# Drive.net
KiCad netlist of a schematic drawn in Altium Designer
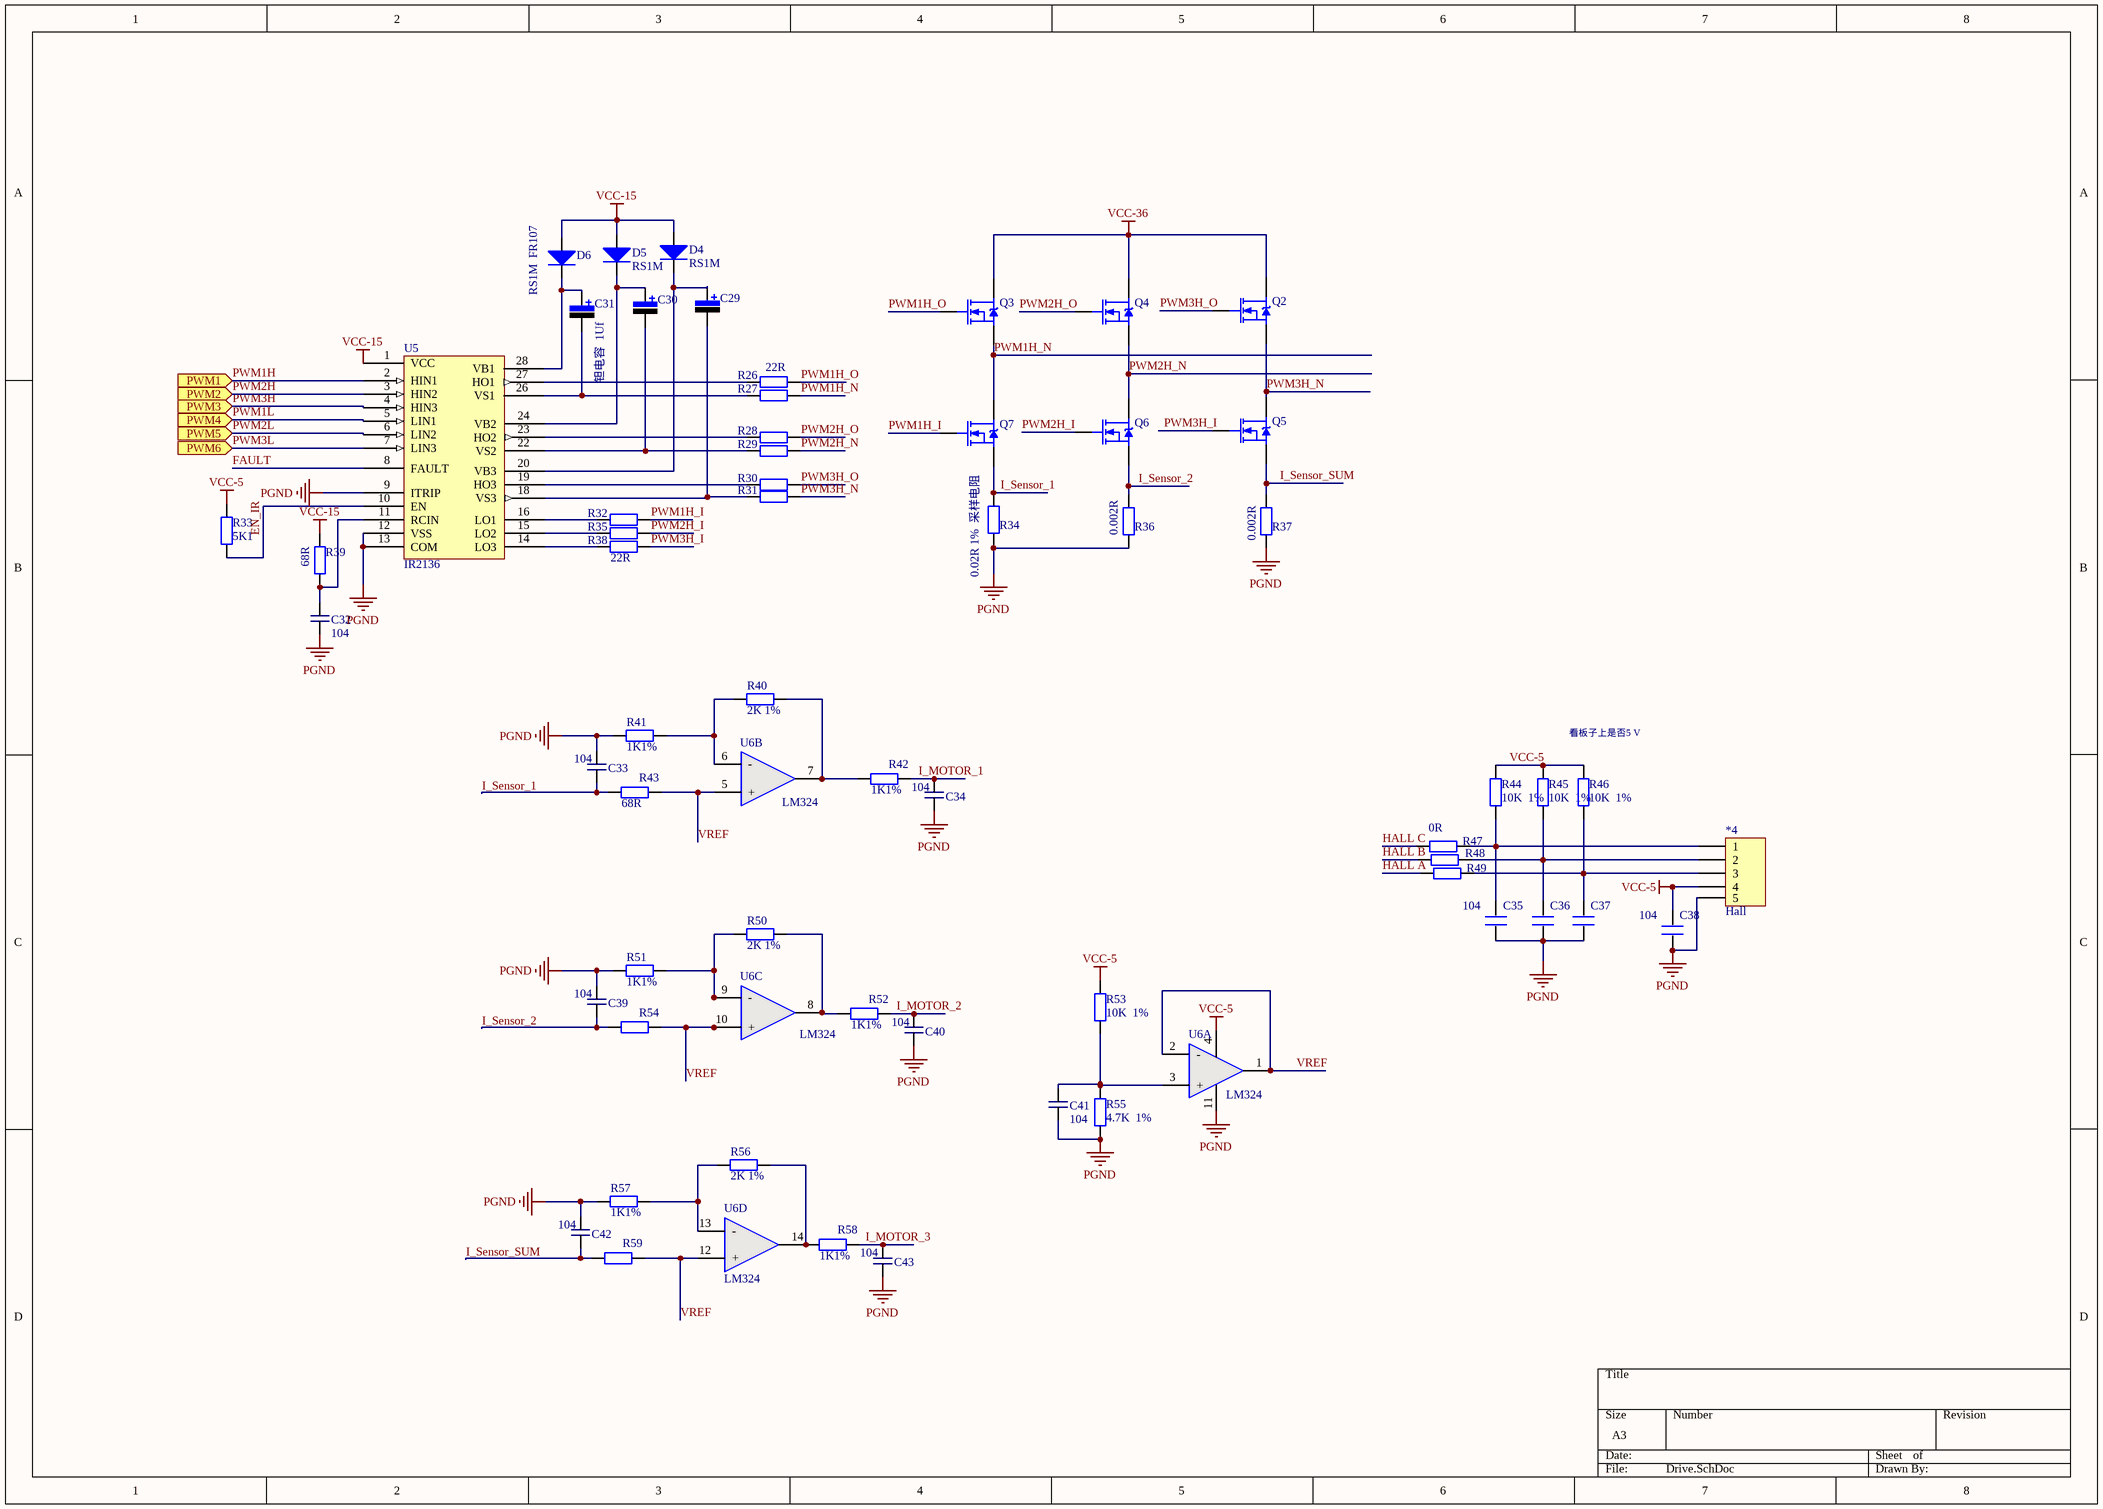
[diagram p0: Drive.SchDoc]

(export (version "E")
  (design (tool "Eeschema 10.0.6"))
  (components
    (comp (ref "*4") (value "Hall") (footprint "普通五口接线柱") (libsource (lib "MySchlib") (part "Head_5")))
    (comp (ref "C29") (value "钽电容") (footprint "3216A  Ta") (libsource (lib "MySchlib") (part "Cap_2")))
    (comp (ref "C30") (value "钽电容") (footprint "3216A  Ta") (libsource (lib "MySchlib") (part "Cap_2")))
    (comp (ref "C31")
      (value "钽电容  1Uf")
      (footprint "3216A  Ta")
      (description "钽电容")
      (libsource (lib "MySchlib") (part "Cap_2"))
    )
    (comp (ref "C32") (value "104") (footprint "0603- C") (libsource (lib "MySchlib") (part "Cap")))
    (comp (ref "C33") (value "104") (footprint "0603- C") (libsource (lib "MySchlib") (part "Cap")))
    (comp (ref "C34") (value "104") (footprint "0603- C") (libsource (lib "MySchlib") (part "Cap")))
    (comp (ref "C35") (value "104") (footprint "0603- C") (libsource (lib "MiniSTM32底板_SCH") (part "C")))
    (comp (ref "C36") (value "104") (footprint "0603- C") (libsource (lib "MiniSTM32底板_SCH") (part "C")))
    (comp (ref "C37") (value "104") (footprint "0603- C") (libsource (lib "MiniSTM32底板_SCH") (part "C")))
    (comp (ref "C38") (value "104") (footprint "0603- C") (libsource (lib "MiniSTM32底板_SCH") (part "C")))
    (comp (ref "C39") (value "104") (footprint "0603- C") (libsource (lib "MySchlib") (part "Cap")))
    (comp (ref "C40") (value "104") (footprint "0603- C") (libsource (lib "MySchlib") (part "Cap")))
    (comp (ref "C41") (value "104") (footprint "0603- C") (libsource (lib "MySchlib") (part "Cap")))
    (comp (ref "C42") (value "104") (footprint "0603- C") (libsource (lib "MySchlib") (part "Cap")))
    (comp (ref "C43") (value "104") (footprint "0603- C") (libsource (lib "MySchlib") (part "Cap")))
    (comp (ref "D4")
      (value "RS1M")
      (footprint "D RS1M")
      (description "二极管")
      (libsource (lib "MySchlib") (part "D_1"))
    )
    (comp (ref "D5")
      (value "RS1M")
      (footprint "D RS1M")
      (description "二极管")
      (libsource (lib "MySchlib") (part "D_1"))
    )
    (comp (ref "D6")
      (value "RS1M  FR107")
      (footprint "D RS1M")
      (description "二极管")
      (libsource (lib "MySchlib") (part "D_1"))
    )
    (comp (ref "Q2")
      (value "IRF540NS")
      (footprint "TO-220AB  MOS")
      (description "MOS")
      (libsource (lib "MySchlib") (part "IRF540NS"))
    )
    (comp (ref "Q3")
      (value "IRF540NS")
      (footprint "TO-220AB  MOS")
      (description "MOS")
      (libsource (lib "MySchlib") (part "IRF540NS"))
    )
    (comp (ref "Q4")
      (value "IRF540NS")
      (footprint "TO-220AB  MOS")
      (description "MOS")
      (libsource (lib "MySchlib") (part "IRF540NS"))
    )
    (comp (ref "Q5")
      (value "IRF540NS")
      (footprint "TO-220AB  MOS")
      (description "MOS")
      (libsource (lib "MySchlib") (part "IRF540NS"))
    )
    (comp (ref "Q6")
      (value "IRF540NS")
      (footprint "TO-220AB  MOS")
      (description "MOS")
      (libsource (lib "MySchlib") (part "IRF540NS"))
    )
    (comp (ref "Q7")
      (value "IRF540NS")
      (footprint "TO-220AB  MOS")
      (description "MOS")
      (libsource (lib "MySchlib") (part "IRF540NS"))
    )
    (comp (ref "R26") (value "22R") (footprint "0805R") (libsource (lib "MySchlib") (part "R")))
    (comp (ref "R27") (value "68R") (footprint "0805R") (libsource (lib "MySchlib") (part "R")))
    (comp (ref "R28") (value "68R") (footprint "0805R") (libsource (lib "MySchlib") (part "R")))
    (comp (ref "R29") (value "68R") (footprint "0805R") (libsource (lib "MySchlib") (part "R")))
    (comp (ref "R30") (value "68R") (footprint "0805R") (libsource (lib "MySchlib") (part "R")))
    (comp (ref "R31") (value "68R") (footprint "0805R") (libsource (lib "MySchlib") (part "R")))
    (comp (ref "R32") (value "68R") (footprint "0805R") (libsource (lib "MySchlib") (part "R")))
    (comp (ref "R33") (value "5K1") (footprint "0603-R") (libsource (lib "") (part "R_2")))
    (comp (ref "R34") (value "0.02R 1%  采样电阻") (footprint "2512R") (libsource (lib "") (part "R_3")))
    (comp (ref "R35") (value "68R") (footprint "0805R") (libsource (lib "MySchlib") (part "R")))
    (comp (ref "R36") (value "0.002R") (footprint "2512R") (libsource (lib "") (part "R_3")))
    (comp (ref "R37") (value "0.002R") (footprint "2512R") (libsource (lib "") (part "R_3")))
    (comp (ref "R38") (value "22R") (footprint "0805R") (libsource (lib "MySchlib") (part "R")))
    (comp (ref "R39") (value "68R") (footprint "0603-R") (libsource (lib "") (part "R_2")))
    (comp (ref "R40") (value "2K 1%") (footprint "0603-R") (libsource (lib "") (part "R_1")))
    (comp (ref "R41") (value "1K1%") (footprint "0603-R") (libsource (lib "") (part "R_1")))
    (comp (ref "R42") (value "1K1%") (footprint "0603-R") (libsource (lib "") (part "R_1")))
    (comp (ref "R43") (value "68R") (footprint "0603-R") (libsource (lib "") (part "R_1")))
    (comp (ref "R44") (value "10K  1%") (footprint "0603-R") (libsource (lib "") (part "R_2")))
    (comp (ref "R45") (value "10K  1%") (footprint "0603-R") (libsource (lib "") (part "R_2")))
    (comp (ref "R46") (value "10K  1%") (footprint "0603-R") (libsource (lib "") (part "R_2")))
    (comp (ref "R47") (value "0R") (footprint "0603-R") (libsource (lib "MySchlib") (part "R")))
    (comp (ref "R48") (value "R") (footprint "0603-R") (libsource (lib "MySchlib") (part "R")))
    (comp (ref "R49") (value "R") (footprint "0603-R") (libsource (lib "MySchlib") (part "R")))
    (comp (ref "R50") (value "2K 1%") (footprint "0603-R") (libsource (lib "") (part "R_1")))
    (comp (ref "R51") (value "1K1%") (footprint "0603-R") (libsource (lib "") (part "R_1")))
    (comp (ref "R52") (value "1K1%") (footprint "0603-R") (libsource (lib "") (part "R_1")))
    (comp (ref "R53") (value "10K  1%") (footprint "0603-R") (libsource (lib "") (part "R_2")))
    (comp (ref "R54") (value "1K1%") (footprint "0603-R") (libsource (lib "") (part "R_1")))
    (comp (ref "R55") (value "4.7K  1%") (footprint "0603-R") (libsource (lib "") (part "R_2")))
    (comp (ref "R56") (value "2K 1%") (footprint "0603-R") (libsource (lib "") (part "R_1")))
    (comp (ref "R57") (value "1K1%") (footprint "0603-R") (libsource (lib "") (part "R_1")))
    (comp (ref "R58") (value "1K1%") (footprint "0603-R") (libsource (lib "") (part "R_1")))
    (comp (ref "R59") (value "1K1%") (footprint "0603-R") (libsource (lib "") (part "R_1")))
    (comp (ref "U5")
      (value "IR2136")
      (footprint "IR2136S SOIC-28")
      (libsource (lib "MySchlib") (part "IR2136"))
    )
    (comp (ref "U6")
      (value "LM324")
      (footprint "SOP-14N")
      (description "4运放SOP8芯片")
      (libsource (lib "MySchlib") (part "LM324"))
    )
  )
  (nets
    (net (code "1") (name "/EN_IR") (class "Default")
      (node (ref "R33") (pin "2") (pinfunction "2_2") (pintype "passive"))
      (node (ref "U5") (pin "10") (pinfunction "EN_10") (pintype "passive"))
    )
    (net (code "2") (name "/FAULT") (class "Default")
      (node (ref "U5") (pin "8") (pinfunction "FAULT_8") (pintype "passive"))
    )
    (net (code "3") (name "/HALL A") (class "Default")
      (node (ref "R49") (pin "1") (pinfunction "1_1") (pintype "passive"))
    )
    (net (code "4") (name "/HALL B") (class "Default")
      (node (ref "R48") (pin "1") (pinfunction "1_1") (pintype "passive"))
    )
    (net (code "5") (name "/HALL C") (class "Default")
      (node (ref "R47") (pin "1") (pinfunction "1_1") (pintype "passive"))
    )
    (net (code "6") (name "/I_MOTOR_1") (class "Default")
      (node (ref "C34") (pin "1") (pinfunction "1_1") (pintype "passive"))
      (node (ref "R42") (pin "1") (pinfunction "1_1") (pintype "passive"))
    )
    (net (code "7") (name "/I_MOTOR_2") (class "Default")
      (node (ref "C40") (pin "1") (pinfunction "1_1") (pintype "passive"))
      (node (ref "R52") (pin "1") (pinfunction "1_1") (pintype "passive"))
    )
    (net (code "8") (name "/I_MOTOR_3") (class "Default")
      (node (ref "C43") (pin "1") (pinfunction "1_1") (pintype "passive"))
      (node (ref "R58") (pin "1") (pinfunction "1_1") (pintype "passive"))
    )
    (net (code "9") (name "/I_Sensor_1") (class "Default")
      (node (ref "C33") (pin "2") (pinfunction "2_2") (pintype "passive"))
      (node (ref "Q7") (pin "S") (pinfunction "S_S") (pintype "passive"))
      (node (ref "R34") (pin "2") (pinfunction "2_2") (pintype "passive"))
      (node (ref "R43") (pin "2") (pinfunction "2_2") (pintype "passive"))
    )
    (net (code "10") (name "/I_Sensor_2") (class "Default")
      (node (ref "C39") (pin "2") (pinfunction "2_2") (pintype "passive"))
      (node (ref "Q6") (pin "S") (pinfunction "S_S") (pintype "passive"))
      (node (ref "R36") (pin "2") (pinfunction "2_2") (pintype "passive"))
      (node (ref "R54") (pin "2") (pinfunction "2_2") (pintype "passive"))
    )
    (net (code "11") (name "/I_Sensor_SUM") (class "Default")
      (node (ref "C42") (pin "2") (pinfunction "2_2") (pintype "passive"))
      (node (ref "Q5") (pin "S") (pinfunction "S_S") (pintype "passive"))
      (node (ref "R37") (pin "2") (pinfunction "2_2") (pintype "passive"))
      (node (ref "R59") (pin "2") (pinfunction "2_2") (pintype "passive"))
    )
    (net (code "12") (name "/PWM1H") (class "Default")
      (node (ref "U5") (pin "2") (pinfunction "HIN1_2") (pintype "input"))
    )
    (net (code "13") (name "/PWM1H_I") (class "Default")
      (node (ref "Q7") (pin "G") (pinfunction "G_G") (pintype "passive"))
      (node (ref "R32") (pin "2") (pinfunction "2_2") (pintype "passive"))
    )
    (net (code "14") (name "/PWM1H_N") (class "Default")
      (node (ref "Q3") (pin "S") (pinfunction "S_S") (pintype "passive"))
      (node (ref "Q7") (pin "D") (pinfunction "D_D") (pintype "passive"))
      (node (ref "R27") (pin "2") (pinfunction "2_2") (pintype "passive"))
    )
    (net (code "15") (name "/PWM1H_O") (class "Default")
      (node (ref "Q3") (pin "G") (pinfunction "G_G") (pintype "passive"))
      (node (ref "R26") (pin "2") (pinfunction "2_2") (pintype "passive"))
    )
    (net (code "16") (name "/PWM1L") (class "Default")
      (node (ref "U5") (pin "5") (pinfunction "LIN1_5") (pintype "input"))
    )
    (net (code "17") (name "/PWM2H") (class "Default")
      (node (ref "U5") (pin "3") (pinfunction "HIN2_3") (pintype "input"))
    )
    (net (code "18") (name "/PWM2H_I") (class "Default")
      (node (ref "Q6") (pin "G") (pinfunction "G_G") (pintype "passive"))
      (node (ref "R35") (pin "2") (pinfunction "2_2") (pintype "passive"))
    )
    (net (code "19") (name "/PWM2H_N") (class "Default")
      (node (ref "Q4") (pin "S") (pinfunction "S_S") (pintype "passive"))
      (node (ref "Q6") (pin "D") (pinfunction "D_D") (pintype "passive"))
      (node (ref "R29") (pin "2") (pinfunction "2_2") (pintype "passive"))
    )
    (net (code "20") (name "/PWM2H_O") (class "Default")
      (node (ref "Q4") (pin "G") (pinfunction "G_G") (pintype "passive"))
      (node (ref "R28") (pin "2") (pinfunction "2_2") (pintype "passive"))
    )
    (net (code "21") (name "/PWM2L") (class "Default")
      (node (ref "U5") (pin "6") (pinfunction "LIN2_6") (pintype "input"))
    )
    (net (code "22") (name "/PWM3H") (class "Default")
      (node (ref "U5") (pin "4") (pinfunction "HIN3_4") (pintype "input"))
    )
    (net (code "23") (name "/PWM3H_I") (class "Default")
      (node (ref "Q5") (pin "G") (pinfunction "G_G") (pintype "passive"))
      (node (ref "R38") (pin "2") (pinfunction "2_2") (pintype "passive"))
    )
    (net (code "24") (name "/PWM3H_N") (class "Default")
      (node (ref "Q2") (pin "S") (pinfunction "S_S") (pintype "passive"))
      (node (ref "Q5") (pin "D") (pinfunction "D_D") (pintype "passive"))
      (node (ref "R31") (pin "2") (pinfunction "2_2") (pintype "passive"))
    )
    (net (code "25") (name "/PWM3H_O") (class "Default")
      (node (ref "Q2") (pin "G") (pinfunction "G_G") (pintype "passive"))
      (node (ref "R30") (pin "2") (pinfunction "2_2") (pintype "passive"))
    )
    (net (code "26") (name "/PWM3L") (class "Default")
      (node (ref "U5") (pin "7") (pinfunction "LIN3_7") (pintype "input"))
    )
    (net (code "27") (name "/VREF") (class "Default")
      (node (ref "R43") (pin "1") (pinfunction "1_1") (pintype "passive"))
      (node (ref "R54") (pin "1") (pinfunction "1_1") (pintype "passive"))
      (node (ref "R59") (pin "1") (pinfunction "1_1") (pintype "passive"))
      (node (ref "U6") (pin "1") (pinfunction "OUT_1") (pintype "passive"))
      (node (ref "U6") (pin "10") (pinfunction "+_10") (pintype "passive"))
      (node (ref "U6") (pin "12") (pinfunction "+_12") (pintype "passive"))
      (node (ref "U6") (pin "2") (pinfunction "-_2") (pintype "passive"))
      (node (ref "U6") (pin "5") (pinfunction "+_5") (pintype "passive"))
    )
    (net (code "28") (name "Net-(*4-Pad1)") (class "Default")
      (node (ref "*4") (pin "1") (pinfunction "1_1") (pintype "passive"))
      (node (ref "C35") (pin "2") (pintype "passive"))
      (node (ref "R44") (pin "2") (pinfunction "2_2") (pintype "passive"))
      (node (ref "R47") (pin "2") (pinfunction "2_2") (pintype "passive"))
    )
    (net (code "29") (name "Net-(*4-Pad2)") (class "Default")
      (node (ref "*4") (pin "2") (pinfunction "2_2") (pintype "passive"))
      (node (ref "C36") (pin "2") (pintype "passive"))
      (node (ref "R45") (pin "2") (pinfunction "2_2") (pintype "passive"))
      (node (ref "R48") (pin "2") (pinfunction "2_2") (pintype "passive"))
    )
    (net (code "30") (name "Net-(*4-Pad3)") (class "Default")
      (node (ref "*4") (pin "3") (pinfunction "3_3") (pintype "passive"))
      (node (ref "C37") (pin "2") (pintype "passive"))
      (node (ref "R46") (pin "2") (pinfunction "2_2") (pintype "passive"))
      (node (ref "R49") (pin "2") (pinfunction "2_2") (pintype "passive"))
    )
    (net (code "31") (name "Net-(U5-HO1)") (class "Default")
      (node (ref "R26") (pin "1") (pinfunction "1_1") (pintype "passive"))
      (node (ref "U5") (pin "27") (pinfunction "HO1_27") (pintype "output"))
    )
    (net (code "32") (name "Net-(U5-HO2)") (class "Default")
      (node (ref "R28") (pin "1") (pinfunction "1_1") (pintype "passive"))
      (node (ref "U5") (pin "23") (pinfunction "HO2_23") (pintype "output"))
    )
    (net (code "33") (name "Net-(U5-HO3)") (class "Default")
      (node (ref "R30") (pin "1") (pinfunction "1_1") (pintype "passive"))
      (node (ref "U5") (pin "19") (pinfunction "HO3_19") (pintype "passive"))
    )
    (net (code "34") (name "Net-(U5-LO1)") (class "Default")
      (node (ref "R32") (pin "1") (pinfunction "1_1") (pintype "passive"))
      (node (ref "U5") (pin "16") (pinfunction "LO1_16") (pintype "passive"))
    )
    (net (code "35") (name "Net-(U5-LO2)") (class "Default")
      (node (ref "R35") (pin "1") (pinfunction "1_1") (pintype "passive"))
      (node (ref "U5") (pin "15") (pinfunction "LO2_15") (pintype "passive"))
    )
    (net (code "36") (name "Net-(U5-LO3)") (class "Default")
      (node (ref "R38") (pin "1") (pinfunction "1_1") (pintype "passive"))
      (node (ref "U5") (pin "14") (pinfunction "LO3_14") (pintype "passive"))
    )
    (net (code "37") (name "Net-(U5-RCIN)") (class "Default")
      (node (ref "C32") (pin "1") (pinfunction "1_1") (pintype "passive"))
      (node (ref "R39") (pin "2") (pinfunction "2_2") (pintype "passive"))
      (node (ref "U5") (pin "11") (pinfunction "RCIN_11") (pintype "passive"))
    )
    (net (code "38") (name "Net-(U5-VB1)") (class "Default")
      (node (ref "C31") (pin "1") (pinfunction "1_1") (pintype "passive"))
      (node (ref "D6") (pin "K") (pinfunction "K_K") (pintype "passive"))
      (node (ref "U5") (pin "28") (pinfunction "VB1_28") (pintype "passive"))
    )
    (net (code "39") (name "Net-(U5-VB2)") (class "Default")
      (node (ref "C30") (pin "1") (pinfunction "1_1") (pintype "passive"))
      (node (ref "D5") (pin "K") (pinfunction "K_K") (pintype "passive"))
      (node (ref "U5") (pin "24") (pinfunction "VB2_24") (pintype "passive"))
    )
    (net (code "40") (name "Net-(U5-VB3)") (class "Default")
      (node (ref "C29") (pin "1") (pinfunction "1_1") (pintype "passive"))
      (node (ref "D4") (pin "K") (pinfunction "K_K") (pintype "passive"))
      (node (ref "U5") (pin "20") (pinfunction "VB3_20") (pintype "passive"))
    )
    (net (code "41") (name "Net-(U5-VS1)") (class "Default")
      (node (ref "C31") (pin "2") (pinfunction "2_2") (pintype "passive"))
      (node (ref "R27") (pin "1") (pinfunction "1_1") (pintype "passive"))
      (node (ref "U5") (pin "26") (pinfunction "VS1_26") (pintype "passive"))
    )
    (net (code "42") (name "Net-(U5-VS2)") (class "Default")
      (node (ref "C30") (pin "2") (pinfunction "2_2") (pintype "passive"))
      (node (ref "R29") (pin "1") (pinfunction "1_1") (pintype "passive"))
      (node (ref "U5") (pin "22") (pinfunction "VS2_22") (pintype "passive"))
    )
    (net (code "43") (name "Net-(U5-VS3)") (class "Default")
      (node (ref "C29") (pin "2") (pinfunction "2_2") (pintype "passive"))
      (node (ref "R31") (pin "1") (pinfunction "1_1") (pintype "passive"))
      (node (ref "U5") (pin "18") (pinfunction "VS3_18") (pintype "output"))
    )
    (net (code "44") (name "Net-(U6A-+)") (class "Default")
      (node (ref "C41") (pin "1") (pinfunction "1_1") (pintype "passive"))
      (node (ref "R53") (pin "2") (pinfunction "2_2") (pintype "passive"))
      (node (ref "R55") (pin "1") (pinfunction "1_1") (pintype "passive"))
      (node (ref "U6") (pin "3") (pinfunction "+_3") (pintype "passive"))
    )
    (net (code "45") (name "Net-(U6B--)") (class "Default")
      (node (ref "R40") (pin "2") (pinfunction "2_2") (pintype "passive"))
      (node (ref "R41") (pin "1") (pinfunction "1_1") (pintype "passive"))
      (node (ref "U6") (pin "6") (pinfunction "-_6") (pintype "passive"))
    )
    (net (code "46") (name "Net-(U6B-OUT)") (class "Default")
      (node (ref "R40") (pin "1") (pinfunction "1_1") (pintype "passive"))
      (node (ref "R42") (pin "2") (pinfunction "2_2") (pintype "passive"))
      (node (ref "U6") (pin "7") (pinfunction "OUT_7") (pintype "passive"))
    )
    (net (code "47") (name "Net-(U6C--)") (class "Default")
      (node (ref "R50") (pin "2") (pinfunction "2_2") (pintype "passive"))
      (node (ref "R51") (pin "1") (pinfunction "1_1") (pintype "passive"))
      (node (ref "U6") (pin "9") (pinfunction "-_9") (pintype "passive"))
    )
    (net (code "48") (name "Net-(U6C-OUT)") (class "Default")
      (node (ref "R50") (pin "1") (pinfunction "1_1") (pintype "passive"))
      (node (ref "R52") (pin "2") (pinfunction "2_2") (pintype "passive"))
      (node (ref "U6") (pin "8") (pinfunction "OUT_8") (pintype "passive"))
    )
    (net (code "49") (name "Net-(U6D--)") (class "Default")
      (node (ref "R56") (pin "2") (pinfunction "2_2") (pintype "passive"))
      (node (ref "R57") (pin "1") (pinfunction "1_1") (pintype "passive"))
      (node (ref "U6") (pin "13") (pinfunction "-_13") (pintype "passive"))
    )
    (net (code "50") (name "Net-(U6D-OUT)") (class "Default")
      (node (ref "R56") (pin "1") (pinfunction "1_1") (pintype "passive"))
      (node (ref "R58") (pin "2") (pinfunction "2_2") (pintype "passive"))
      (node (ref "U6") (pin "14") (pinfunction "OUT_14") (pintype "passive"))
    )
    (net (code "51") (name "PGND") (class "Default")
      (node (ref "*4") (pin "5") (pinfunction "5_5") (pintype "passive"))
      (node (ref "C32") (pin "2") (pinfunction "2_2") (pintype "passive"))
      (node (ref "C33") (pin "1") (pinfunction "1_1") (pintype "passive"))
      (node (ref "C34") (pin "2") (pinfunction "2_2") (pintype "passive"))
      (node (ref "C35") (pin "1") (pintype "passive"))
      (node (ref "C36") (pin "1") (pintype "passive"))
      (node (ref "C37") (pin "1") (pintype "passive"))
      (node (ref "C38") (pin "1") (pintype "passive"))
      (node (ref "C39") (pin "1") (pinfunction "1_1") (pintype "passive"))
      (node (ref "C40") (pin "2") (pinfunction "2_2") (pintype "passive"))
      (node (ref "C41") (pin "2") (pinfunction "2_2") (pintype "passive"))
      (node (ref "C42") (pin "1") (pinfunction "1_1") (pintype "passive"))
      (node (ref "C43") (pin "2") (pinfunction "2_2") (pintype "passive"))
      (node (ref "R34") (pin "1") (pinfunction "1_1") (pintype "passive"))
      (node (ref "R36") (pin "1") (pinfunction "1_1") (pintype "passive"))
      (node (ref "R37") (pin "1") (pinfunction "1_1") (pintype "passive"))
      (node (ref "R41") (pin "2") (pinfunction "2_2") (pintype "passive"))
      (node (ref "R51") (pin "2") (pinfunction "2_2") (pintype "passive"))
      (node (ref "R55") (pin "2") (pinfunction "2_2") (pintype "passive"))
      (node (ref "R57") (pin "2") (pinfunction "2_2") (pintype "passive"))
      (node (ref "U5") (pin "12") (pinfunction "VSS_12") (pintype "passive"))
      (node (ref "U5") (pin "13") (pinfunction "COM_13") (pintype "passive"))
      (node (ref "U5") (pin "9") (pinfunction "ITRIP_9") (pintype "passive"))
      (node (ref "U6") (pin "11") (pinfunction "V-_11") (pintype "passive"))
    )
    (net (code "52") (name "VCC-5") (class "Default")
      (node (ref "*4") (pin "4") (pinfunction "4_4") (pintype "passive"))
      (node (ref "C38") (pin "2") (pintype "passive"))
      (node (ref "R33") (pin "1") (pinfunction "1_1") (pintype "passive"))
      (node (ref "R44") (pin "1") (pinfunction "1_1") (pintype "passive"))
      (node (ref "R45") (pin "1") (pinfunction "1_1") (pintype "passive"))
      (node (ref "R46") (pin "1") (pinfunction "1_1") (pintype "passive"))
      (node (ref "R53") (pin "1") (pinfunction "1_1") (pintype "passive"))
      (node (ref "U6") (pin "4") (pinfunction "V+_4") (pintype "passive"))
    )
    (net (code "53") (name "VCC-15") (class "Default")
      (node (ref "D4") (pin "A") (pinfunction "A_A") (pintype "passive"))
      (node (ref "D5") (pin "A") (pinfunction "A_A") (pintype "passive"))
      (node (ref "D6") (pin "A") (pinfunction "A_A") (pintype "passive"))
      (node (ref "R39") (pin "1") (pinfunction "1_1") (pintype "passive"))
      (node (ref "U5") (pin "1") (pinfunction "VCC_1") (pintype "passive"))
    )
    (net (code "54") (name "VCC-36") (class "Default")
      (node (ref "Q2") (pin "D") (pinfunction "D_D") (pintype "passive"))
      (node (ref "Q3") (pin "D") (pinfunction "D_D") (pintype "passive"))
      (node (ref "Q4") (pin "D") (pinfunction "D_D") (pintype "passive"))
    )
  )
)
